# Schematic.net
KiCad netlist of a schematic drawn in EAGLE
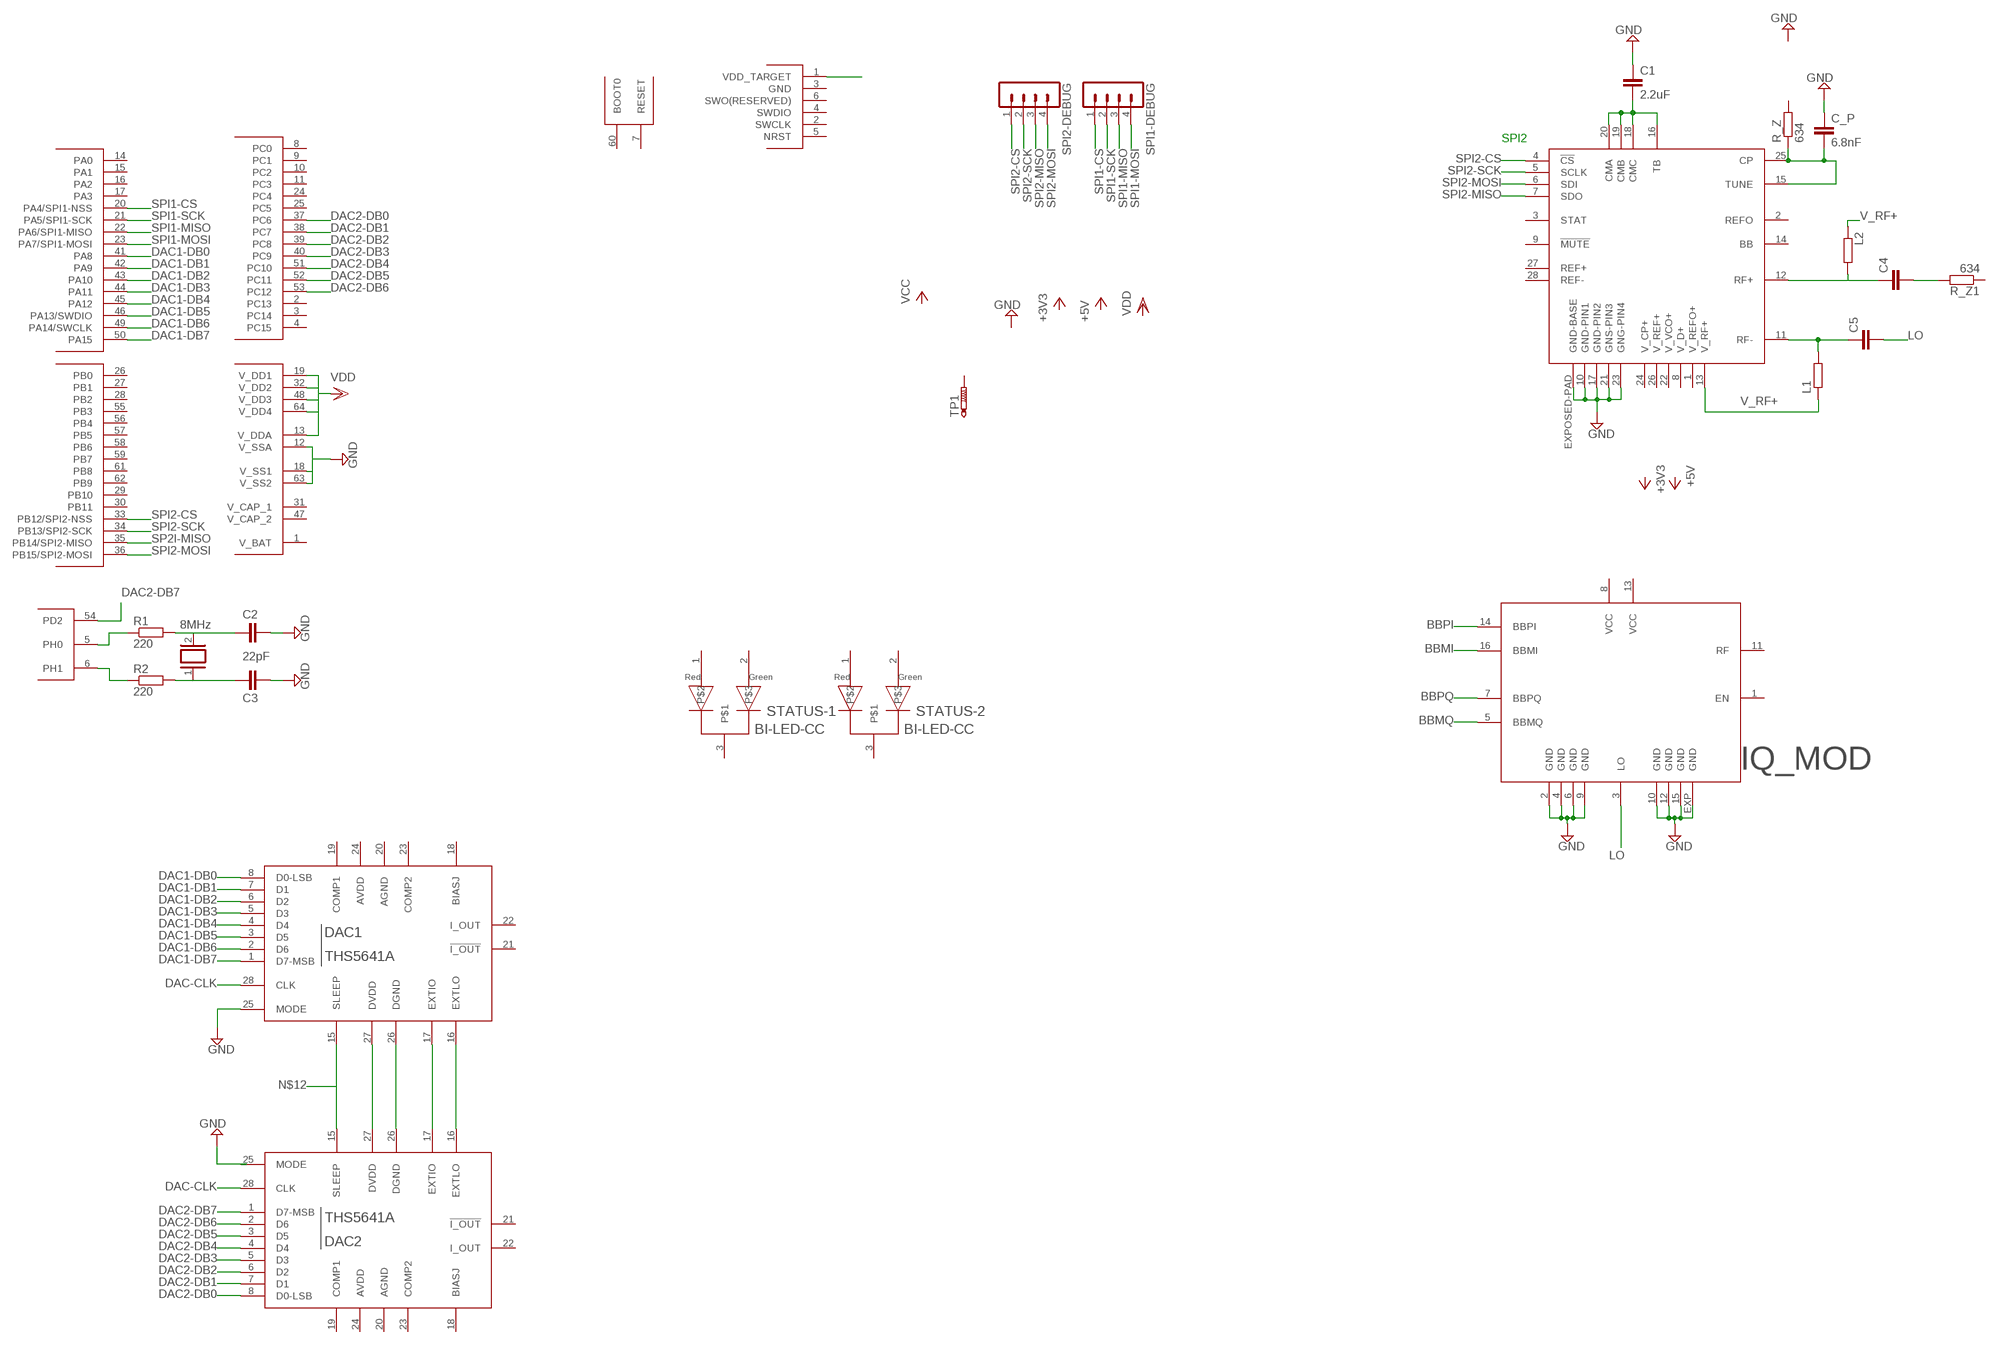
[diagram p0: schematic, sheet 1]

(export (version "E")
  (design (tool "Eeschema 10.0.6"))
  (components
    (comp (ref "C1")
      (value "2.2uF")
      (footprint "eagle-import:C0603")
      (libsource (lib "eagle-import") (part "C-EUC0603"))
    )
    (comp (ref "C2")
      (value "22pF")
      (footprint "eagle-import:C0603")
      (libsource (lib "eagle-import") (part "resistor_C-EUC0603"))
    )
    (comp (ref "C3")
      (value "22pF")
      (footprint "eagle-import:C0603")
      (libsource (lib "eagle-import") (part "resistor_C-EUC0603"))
    )
    (comp (ref "C4")
      (value "C-EUC1210")
      (footprint "eagle-import:C1210")
      (libsource (lib "eagle-import") (part "C-EUC1210"))
    )
    (comp (ref "C5")
      (value "C-EUC1210")
      (footprint "eagle-import:C1210")
      (libsource (lib "eagle-import") (part "C-EUC1210"))
    )
    (comp (ref "C_P")
      (value "6.8nF")
      (footprint "eagle-import:C0805")
      (libsource (lib "eagle-import") (part "resistor_C-EUC0805"))
    )
    (comp (ref "DAC1")
      (value "THS5641A")
      (footprint "eagle-import:SO28")
      (libsource (lib "eagle-import") (part "THS5641A"))
    )
    (comp (ref "DAC2")
      (value "THS5641A")
      (footprint "eagle-import:SO28")
      (libsource (lib "eagle-import") (part "THS5641A"))
    )
    (comp (ref "IQ_MOD")
      (value "LT5568")
      (footprint "eagle-import:QFN-16")
      (libsource (lib "eagle-import") (part "LT5568"))
    )
    (comp (ref "L1")
      (value "R-EU_R0402")
      (footprint "eagle-import:R0402")
      (libsource (lib "eagle-import") (part "R-EU_R0402"))
    )
    (comp (ref "L2")
      (value "R-EU_R0402")
      (footprint "eagle-import:R0402")
      (libsource (lib "eagle-import") (part "R-EU_R0402"))
    )
    (comp (ref "Q1")
      (value "8MHz")
      (footprint "eagle-import:QS")
      (libsource (lib "eagle-import") (part "XTAL/S"))
    )
    (comp (ref "R1")
      (value "220")
      (footprint "eagle-import:R0603")
      (libsource (lib "eagle-import") (part "resistor_R-EU_R0603"))
    )
    (comp (ref "R2")
      (value "220")
      (footprint "eagle-import:R0603")
      (libsource (lib "eagle-import") (part "resistor_R-EU_R0603"))
    )
    (comp (ref "R_Z")
      (value "634")
      (footprint "eagle-import:R0805")
      (libsource (lib "eagle-import") (part "R-EU_R0805"))
    )
    (comp (ref "R_Z1")
      (value "634")
      (footprint "eagle-import:R0805")
      (libsource (lib "eagle-import") (part "R-EU_R0805"))
    )
    (comp (ref "SPI1-DEBUG")
      (value "MA04-1")
      (footprint "eagle-import:MA04-1")
      (libsource (lib "eagle-import") (part "MA04-1"))
    )
    (comp (ref "SPI2-DEBUG")
      (value "MA04-1")
      (footprint "eagle-import:MA04-1")
      (libsource (lib "eagle-import") (part "MA04-1"))
    )
    (comp (ref "STATUS-1")
      (value "BI-LED-CC")
      (footprint "eagle-import:SOT-23")
      (libsource (lib "eagle-import") (part "BI-LED-CC"))
    )
    (comp (ref "STATUS-2")
      (value "BI-LED-CC")
      (footprint "eagle-import:SOT-23")
      (libsource (lib "eagle-import") (part "BI-LED-CC"))
    )
    (comp (ref "TP1")
      (value "PTR1PAD1-20Y")
      (footprint "eagle-import:P1-20Y")
      (libsource (lib "eagle-import") (part "PTR1PAD1-20Y"))
    )
    (comp (ref "U$1")
      (value "STM32F415RGT6")
      (footprint "eagle-import:LQFP-64")
      (libsource (lib "eagle-import") (part "STM32F415RGT6"))
    )
    (comp (ref "U$2")
      (value "SWD-HEADER")
      (footprint "eagle-import:6PIN-HEADER")
      (libsource (lib "eagle-import") (part "SWD-HEADER"))
    )
    (comp (ref "U$3")
      (value "LTC6946")
      (footprint "eagle-import:QFN-28")
      (libsource (lib "eagle-import") (part "LTC6946"))
    )
  )
  (nets
    (net (code "3") (name "/BBMI") (class "Default")
      (node (ref "IQ_MOD") (pin "16") (pinfunction "BBMI_16") (pintype "bidirectional"))
    )
    (net (code "4") (name "/BBMQ") (class "Default")
      (node (ref "IQ_MOD") (pin "5") (pinfunction "BBMQ_5") (pintype "bidirectional"))
    )
    (net (code "5") (name "/BBPI") (class "Default")
      (node (ref "IQ_MOD") (pin "14") (pinfunction "BBPI_14") (pintype "bidirectional"))
    )
    (net (code "6") (name "/BBPQ") (class "Default")
      (node (ref "IQ_MOD") (pin "7") (pinfunction "BBPQ_7") (pintype "bidirectional"))
    )
    (net (code "7") (name "/DAC-CLK") (class "Default")
      (node (ref "DAC1") (pin "28") (pinfunction "CLK_28") (pintype "bidirectional"))
      (node (ref "DAC2") (pin "28") (pinfunction "CLK_28") (pintype "bidirectional"))
    )
    (net (code "8") (name "/DAC1-DB0") (class "Default")
      (node (ref "DAC1") (pin "8") (pinfunction "D0-LSB_8") (pintype "bidirectional"))
      (node (ref "U$1") (pin "41") (pinfunction "PA8_41") (pintype "bidirectional"))
    )
    (net (code "9") (name "/DAC1-DB1") (class "Default")
      (node (ref "DAC1") (pin "7") (pinfunction "D1_7") (pintype "bidirectional"))
      (node (ref "U$1") (pin "42") (pinfunction "PA9_42") (pintype "bidirectional"))
    )
    (net (code "10") (name "/DAC1-DB2") (class "Default")
      (node (ref "DAC1") (pin "6") (pinfunction "D2_6") (pintype "bidirectional"))
      (node (ref "U$1") (pin "43") (pinfunction "PA10_43") (pintype "bidirectional"))
    )
    (net (code "11") (name "/DAC1-DB3") (class "Default")
      (node (ref "DAC1") (pin "5") (pinfunction "D3_5") (pintype "bidirectional"))
      (node (ref "U$1") (pin "44") (pinfunction "PA11_44") (pintype "bidirectional"))
    )
    (net (code "12") (name "/DAC1-DB4") (class "Default")
      (node (ref "DAC1") (pin "4") (pinfunction "D4_4") (pintype "bidirectional"))
      (node (ref "U$1") (pin "45") (pinfunction "PA12_45") (pintype "bidirectional"))
    )
    (net (code "13") (name "/DAC1-DB5") (class "Default")
      (node (ref "DAC1") (pin "3") (pinfunction "D5_3") (pintype "bidirectional"))
      (node (ref "U$1") (pin "46") (pinfunction "PA13/SWDIO_46") (pintype "bidirectional"))
    )
    (net (code "14") (name "/DAC1-DB6") (class "Default")
      (node (ref "DAC1") (pin "2") (pinfunction "D6_2") (pintype "bidirectional"))
      (node (ref "U$1") (pin "49") (pinfunction "PA14/SWCLK_49") (pintype "bidirectional"))
    )
    (net (code "15") (name "/DAC1-DB7") (class "Default")
      (node (ref "DAC1") (pin "1") (pinfunction "D7-MSB_1") (pintype "bidirectional"))
      (node (ref "U$1") (pin "50") (pinfunction "PA15_50") (pintype "bidirectional"))
    )
    (net (code "16") (name "/DAC2-DB0") (class "Default")
      (node (ref "DAC2") (pin "8") (pinfunction "D0-LSB_8") (pintype "bidirectional"))
      (node (ref "U$1") (pin "37") (pinfunction "PC6_37") (pintype "bidirectional"))
    )
    (net (code "17") (name "/DAC2-DB1") (class "Default")
      (node (ref "DAC2") (pin "7") (pinfunction "D1_7") (pintype "bidirectional"))
      (node (ref "U$1") (pin "38") (pinfunction "PC7_38") (pintype "bidirectional"))
    )
    (net (code "18") (name "/DAC2-DB2") (class "Default")
      (node (ref "DAC2") (pin "6") (pinfunction "D2_6") (pintype "bidirectional"))
      (node (ref "U$1") (pin "39") (pinfunction "PC8_39") (pintype "bidirectional"))
    )
    (net (code "19") (name "/DAC2-DB3") (class "Default")
      (node (ref "DAC2") (pin "5") (pinfunction "D3_5") (pintype "bidirectional"))
      (node (ref "U$1") (pin "40") (pinfunction "PC9_40") (pintype "bidirectional"))
    )
    (net (code "20") (name "/DAC2-DB4") (class "Default")
      (node (ref "DAC2") (pin "4") (pinfunction "D4_4") (pintype "bidirectional"))
      (node (ref "U$1") (pin "51") (pinfunction "PC10_51") (pintype "bidirectional"))
    )
    (net (code "21") (name "/DAC2-DB5") (class "Default")
      (node (ref "DAC2") (pin "3") (pinfunction "D5_3") (pintype "bidirectional"))
      (node (ref "U$1") (pin "52") (pinfunction "PC11_52") (pintype "bidirectional"))
    )
    (net (code "22") (name "/DAC2-DB6") (class "Default")
      (node (ref "DAC2") (pin "2") (pinfunction "D6_2") (pintype "bidirectional"))
      (node (ref "U$1") (pin "53") (pinfunction "PC12_53") (pintype "bidirectional"))
    )
    (net (code "23") (name "/DAC2-DB7") (class "Default")
      (node (ref "DAC2") (pin "1") (pinfunction "D7-MSB_1") (pintype "bidirectional"))
      (node (ref "U$1") (pin "54") (pinfunction "PD2_54") (pintype "bidirectional"))
    )
    (net (code "24") (name "/LO") (class "Default")
      (node (ref "C5") (pin "2") (pinfunction "2_2") (pintype "passive"))
      (node (ref "IQ_MOD") (pin "3") (pinfunction "LO_3") (pintype "bidirectional"))
    )
    (net (code "25") (name "/N$12") (class "Default")
      (node (ref "DAC1") (pin "15") (pinfunction "SLEEP_15") (pintype "bidirectional"))
      (node (ref "DAC2") (pin "15") (pinfunction "SLEEP_15") (pintype "bidirectional"))
    )
    (net (code "26") (name "/SP2I-MISO") (class "Default")
      (node (ref "U$1") (pin "35") (pinfunction "PB14/SPI2-MISO_35") (pintype "bidirectional"))
    )
    (net (code "27") (name "/SPI1-CS") (class "Default")
      (node (ref "SPI1-DEBUG") (pin "1") (pinfunction "1_1") (pintype "passive"))
      (node (ref "U$1") (pin "20") (pinfunction "PA4/SPI1-NSS_20") (pintype "bidirectional"))
    )
    (net (code "28") (name "/SPI1-MISO") (class "Default")
      (node (ref "SPI1-DEBUG") (pin "3") (pinfunction "3_3") (pintype "passive"))
      (node (ref "U$1") (pin "22") (pinfunction "PA6/SPI1-MISO_22") (pintype "bidirectional"))
    )
    (net (code "29") (name "/SPI1-MOSI") (class "Default")
      (node (ref "SPI1-DEBUG") (pin "4") (pinfunction "4_4") (pintype "passive"))
      (node (ref "U$1") (pin "23") (pinfunction "PA7/SPI1-MOSI_23") (pintype "bidirectional"))
    )
    (net (code "30") (name "/SPI1-SCK") (class "Default")
      (node (ref "SPI1-DEBUG") (pin "2") (pinfunction "2_2") (pintype "passive"))
      (node (ref "U$1") (pin "21") (pinfunction "PA5/SPI1-SCK_21") (pintype "bidirectional"))
    )
    (net (code "31") (name "/SPI2-CS") (class "Default")
      (node (ref "SPI2-DEBUG") (pin "1") (pinfunction "1_1") (pintype "passive"))
      (node (ref "U$1") (pin "33") (pinfunction "PB12/SPI2-NSS_33") (pintype "bidirectional"))
      (node (ref "U$3") (pin "4") (pinfunction "~{CS}_4") (pintype "bidirectional"))
    )
    (net (code "32") (name "/SPI2-MISO") (class "Default")
      (node (ref "SPI2-DEBUG") (pin "3") (pinfunction "3_3") (pintype "passive"))
      (node (ref "U$3") (pin "7") (pinfunction "SDO_7") (pintype "bidirectional"))
    )
    (net (code "33") (name "/SPI2-MOSI") (class "Default")
      (node (ref "SPI2-DEBUG") (pin "4") (pinfunction "4_4") (pintype "passive"))
      (node (ref "U$1") (pin "36") (pinfunction "PB15/SPI2-MOSI_36") (pintype "bidirectional"))
      (node (ref "U$3") (pin "6") (pinfunction "SDI_6") (pintype "bidirectional"))
    )
    (net (code "34") (name "/SPI2-SCK") (class "Default")
      (node (ref "SPI2-DEBUG") (pin "2") (pinfunction "2_2") (pintype "passive"))
      (node (ref "U$1") (pin "34") (pinfunction "PB13/SPI2-SCK_34") (pintype "bidirectional"))
      (node (ref "U$3") (pin "5") (pinfunction "SCLK_5") (pintype "bidirectional"))
    )
    (net (code "35") (name "/V_RF+") (class "Default")
      (node (ref "L1") (pin "1") (pinfunction "1_1") (pintype "passive"))
      (node (ref "L2") (pin "1") (pinfunction "1_1") (pintype "passive"))
      (node (ref "U$3") (pin "13") (pinfunction "V_RF+_13") (pintype "bidirectional"))
    )
    (net (code "36") (name "GND") (class "Default")
      (node (ref "C1") (pin "1") (pinfunction "1_1") (pintype "passive"))
      (node (ref "C2") (pin "2") (pinfunction "2_2") (pintype "passive"))
      (node (ref "C3") (pin "2") (pinfunction "2_2") (pintype "passive"))
      (node (ref "C_P") (pin "1") (pinfunction "1_1") (pintype "passive"))
      (node (ref "DAC1") (pin "25") (pinfunction "MODE_25") (pintype "bidirectional"))
      (node (ref "IQ_MOD") (pin "10") (pinfunction "GND_10") (pintype "bidirectional"))
      (node (ref "IQ_MOD") (pin "12") (pinfunction "GND_12") (pintype "bidirectional"))
      (node (ref "IQ_MOD") (pin "15") (pinfunction "GND_15") (pintype "bidirectional"))
      (node (ref "IQ_MOD") (pin "2") (pinfunction "GND_2") (pintype "bidirectional"))
      (node (ref "IQ_MOD") (pin "4") (pinfunction "GND_4") (pintype "bidirectional"))
      (node (ref "IQ_MOD") (pin "6") (pinfunction "GND_6") (pintype "bidirectional"))
      (node (ref "IQ_MOD") (pin "9") (pinfunction "GND_9") (pintype "bidirectional"))
      (node (ref "IQ_MOD") (pin "EXP") (pinfunction "GND_EXP") (pintype "bidirectional"))
      (node (ref "U$1") (pin "12") (pinfunction "V_SSA_12") (pintype "bidirectional"))
      (node (ref "U$1") (pin "18") (pinfunction "V_SS1_18") (pintype "bidirectional"))
      (node (ref "U$1") (pin "63") (pinfunction "V_SS2_63") (pintype "bidirectional"))
      (node (ref "U$3") (pin "10") (pinfunction "GND-PIN1_10") (pintype "bidirectional"))
      (node (ref "U$3") (pin "17") (pinfunction "GND-PIN2_17") (pintype "bidirectional"))
      (node (ref "U$3") (pin "21") (pinfunction "GNS-PIN3_21") (pintype "bidirectional"))
      (node (ref "U$3") (pin "23") (pinfunction "GNG-PIN4_23") (pintype "bidirectional"))
      (node (ref "U$3") (pin "EXPOSED-PAD") (pinfunction "GND-BASE_EXPOSED-PAD") (pintype "bidirectional"))
    )
    (net (code "37") (name "Net-(C2-Pad1)") (class "Default")
      (node (ref "C2") (pin "1") (pinfunction "1_1") (pintype "passive"))
      (node (ref "Q1") (pin "2") (pinfunction "2_2") (pintype "passive"))
      (node (ref "R1") (pin "2") (pinfunction "2_2") (pintype "passive"))
    )
    (net (code "38") (name "Net-(C3-Pad1)") (class "Default")
      (node (ref "C3") (pin "1") (pinfunction "1_1") (pintype "passive"))
      (node (ref "Q1") (pin "1") (pinfunction "1_1") (pintype "passive"))
      (node (ref "R2") (pin "2") (pinfunction "2_2") (pintype "passive"))
    )
    (net (code "39") (name "Net-(C4-Pad2)") (class "Default")
      (node (ref "C4") (pin "2") (pinfunction "2_2") (pintype "passive"))
      (node (ref "R_Z1") (pin "2") (pinfunction "2_2") (pintype "passive"))
    )
    (net (code "40") (name "Net-(DAC1-DGND)") (class "Default")
      (node (ref "DAC1") (pin "26") (pinfunction "DGND_26") (pintype "bidirectional"))
      (node (ref "DAC2") (pin "26") (pinfunction "DGND_26") (pintype "bidirectional"))
    )
    (net (code "41") (name "Net-(DAC1-DVDD)") (class "Default")
      (node (ref "DAC1") (pin "27") (pinfunction "DVDD_27") (pintype "bidirectional"))
      (node (ref "DAC2") (pin "27") (pinfunction "DVDD_27") (pintype "bidirectional"))
    )
    (net (code "42") (name "Net-(DAC1-EXTIO)") (class "Default")
      (node (ref "DAC1") (pin "17") (pinfunction "EXTIO_17") (pintype "bidirectional"))
      (node (ref "DAC2") (pin "17") (pinfunction "EXTIO_17") (pintype "bidirectional"))
    )
    (net (code "43") (name "Net-(DAC1-EXTLO)") (class "Default")
      (node (ref "DAC1") (pin "16") (pinfunction "EXTLO_16") (pintype "bidirectional"))
      (node (ref "DAC2") (pin "16") (pinfunction "EXTLO_16") (pintype "bidirectional"))
    )
    (net (code "44") (name "Net-(U$1B-PH0)") (class "Default")
      (node (ref "R1") (pin "1") (pinfunction "1_1") (pintype "passive"))
      (node (ref "U$1") (pin "5") (pinfunction "PH0_5") (pintype "bidirectional"))
    )
    (net (code "45") (name "Net-(U$1B-PH1)") (class "Default")
      (node (ref "R2") (pin "1") (pinfunction "1_1") (pintype "passive"))
      (node (ref "U$1") (pin "6") (pinfunction "PH1_6") (pintype "bidirectional"))
    )
    (net (code "46") (name "Net-(U$3-CMA)") (class "Default")
      (node (ref "C1") (pin "2") (pinfunction "2_2") (pintype "passive"))
      (node (ref "U$3") (pin "16") (pinfunction "TB_16") (pintype "bidirectional"))
      (node (ref "U$3") (pin "18") (pinfunction "CMC_18") (pintype "bidirectional"))
      (node (ref "U$3") (pin "19") (pinfunction "CMB_19") (pintype "bidirectional"))
      (node (ref "U$3") (pin "20") (pinfunction "CMA_20") (pintype "bidirectional"))
    )
    (net (code "47") (name "Net-(U$3-CP)") (class "Default")
      (node (ref "C_P") (pin "2") (pinfunction "2_2") (pintype "passive"))
      (node (ref "R_Z") (pin "1") (pinfunction "1_1") (pintype "passive"))
      (node (ref "U$3") (pin "15") (pinfunction "TUNE_15") (pintype "bidirectional"))
      (node (ref "U$3") (pin "25") (pinfunction "CP_25") (pintype "bidirectional"))
    )
    (net (code "48") (name "Net-(U$3-RF+)") (class "Default")
      (node (ref "C4") (pin "1") (pinfunction "1_1") (pintype "passive"))
      (node (ref "L2") (pin "2") (pinfunction "2_2") (pintype "passive"))
      (node (ref "U$3") (pin "12") (pinfunction "RF+_12") (pintype "bidirectional"))
    )
    (net (code "49") (name "Net-(U$3-RF-)") (class "Default")
      (node (ref "C5") (pin "1") (pinfunction "1_1") (pintype "passive"))
      (node (ref "L1") (pin "2") (pinfunction "2_2") (pintype "passive"))
      (node (ref "U$3") (pin "11") (pinfunction "RF-_11") (pintype "bidirectional"))
    )
    (net (code "51") (name "VDD") (class "Default")
      (node (ref "U$1") (pin "13") (pinfunction "V_DDA_13") (pintype "bidirectional"))
      (node (ref "U$1") (pin "19") (pinfunction "V_DD1_19") (pintype "bidirectional"))
      (node (ref "U$1") (pin "32") (pinfunction "V_DD2_32") (pintype "bidirectional"))
      (node (ref "U$1") (pin "48") (pinfunction "V_DD3_48") (pintype "bidirectional"))
      (node (ref "U$1") (pin "64") (pinfunction "V_DD4_64") (pintype "bidirectional"))
    )
    (net (code "52") (name "unconnected-(DAC1-AGND-Pad20)") (class "Default")
      (node (ref "DAC1") (pin "20") (pinfunction "AGND_20") (pintype "bidirectional"))
    )
    (net (code "53") (name "unconnected-(DAC1-AVDD-Pad24)") (class "Default")
      (node (ref "DAC1") (pin "24") (pinfunction "AVDD_24") (pintype "bidirectional"))
    )
    (net (code "54") (name "unconnected-(DAC1-BIASJ-Pad18)") (class "Default")
      (node (ref "DAC1") (pin "18") (pinfunction "BIASJ_18") (pintype "bidirectional"))
    )
    (net (code "55") (name "unconnected-(DAC1-COMP1-Pad19)") (class "Default")
      (node (ref "DAC1") (pin "19") (pinfunction "COMP1_19") (pintype "bidirectional"))
    )
    (net (code "56") (name "unconnected-(DAC1-COMP2-Pad23)") (class "Default")
      (node (ref "DAC1") (pin "23") (pinfunction "COMP2_23") (pintype "bidirectional"))
    )
    (net (code "57") (name "unconnected-(DAC1-I_OUT-Pad22)") (class "Default")
      (node (ref "DAC1") (pin "22") (pinfunction "I_OUT_22") (pintype "bidirectional"))
    )
    (net (code "58") (name "unconnected-(DAC1-~{I_OUT}-Pad21)") (class "Default")
      (node (ref "DAC1") (pin "21") (pinfunction "~{I_OUT}_21") (pintype "bidirectional"))
    )
    (net (code "59") (name "unconnected-(DAC2-AGND-Pad20)") (class "Default")
      (node (ref "DAC2") (pin "20") (pinfunction "AGND_20") (pintype "bidirectional"))
    )
    (net (code "60") (name "unconnected-(DAC2-AVDD-Pad24)") (class "Default")
      (node (ref "DAC2") (pin "24") (pinfunction "AVDD_24") (pintype "bidirectional"))
    )
    (net (code "61") (name "unconnected-(DAC2-BIASJ-Pad18)") (class "Default")
      (node (ref "DAC2") (pin "18") (pinfunction "BIASJ_18") (pintype "bidirectional"))
    )
    (net (code "62") (name "unconnected-(DAC2-COMP1-Pad19)") (class "Default")
      (node (ref "DAC2") (pin "19") (pinfunction "COMP1_19") (pintype "bidirectional"))
    )
    (net (code "63") (name "unconnected-(DAC2-COMP2-Pad23)") (class "Default")
      (node (ref "DAC2") (pin "23") (pinfunction "COMP2_23") (pintype "bidirectional"))
    )
    (net (code "64") (name "unconnected-(DAC2-I_OUT-Pad22)") (class "Default")
      (node (ref "DAC2") (pin "22") (pinfunction "I_OUT_22") (pintype "bidirectional"))
    )
    (net (code "65") (name "unconnected-(DAC2-MODE-Pad25)") (class "Default")
      (node (ref "DAC2") (pin "25") (pinfunction "MODE_25") (pintype "bidirectional"))
    )
    (net (code "66") (name "unconnected-(DAC2-~{I_OUT}-Pad21)") (class "Default")
      (node (ref "DAC2") (pin "21") (pinfunction "~{I_OUT}_21") (pintype "bidirectional"))
    )
    (net (code "67") (name "unconnected-(IQ_MOD-EN-Pad1)") (class "Default")
      (node (ref "IQ_MOD") (pin "1") (pinfunction "EN_1") (pintype "bidirectional"))
    )
    (net (code "68") (name "unconnected-(IQ_MOD-RF-Pad11)") (class "Default")
      (node (ref "IQ_MOD") (pin "11") (pinfunction "RF_11") (pintype "bidirectional"))
    )
    (net (code "69") (name "unconnected-(IQ_MOD-VCC-Pad8)") (class "Default")
      (node (ref "IQ_MOD") (pin "8") (pinfunction "VCC_8") (pintype "bidirectional"))
    )
    (net (code "70") (name "unconnected-(IQ_MOD-VCC-Pad13)") (class "Default")
      (node (ref "IQ_MOD") (pin "13") (pinfunction "VCC_13") (pintype "bidirectional"))
    )
    (net (code "71") (name "unconnected-(R_Z-Pad2)") (class "Default")
      (node (ref "R_Z") (pin "2") (pinfunction "2_2") (pintype "passive"))
    )
    (net (code "72") (name "unconnected-(R_Z1-Pad1)") (class "Default")
      (node (ref "R_Z1") (pin "1") (pinfunction "1_1") (pintype "passive"))
    )
    (net (code "73") (name "unconnected-(STATUS-1-P$1-Pad3)") (class "Default")
      (node (ref "STATUS-1") (pin "3") (pinfunction "P$1_3") (pintype "bidirectional"))
    )
    (net (code "74") (name "unconnected-(STATUS-1-P$2-Pad1)") (class "Default")
      (node (ref "STATUS-1") (pin "1") (pinfunction "P$2_1") (pintype "bidirectional"))
    )
    (net (code "75") (name "unconnected-(STATUS-1-P$3-Pad2)") (class "Default")
      (node (ref "STATUS-1") (pin "2") (pinfunction "P$3_2") (pintype "bidirectional"))
    )
    (net (code "76") (name "unconnected-(STATUS-2-P$1-Pad3)") (class "Default")
      (node (ref "STATUS-2") (pin "3") (pinfunction "P$1_3") (pintype "bidirectional"))
    )
    (net (code "77") (name "unconnected-(STATUS-2-P$2-Pad1)") (class "Default")
      (node (ref "STATUS-2") (pin "1") (pinfunction "P$2_1") (pintype "bidirectional"))
    )
    (net (code "78") (name "unconnected-(STATUS-2-P$3-Pad2)") (class "Default")
      (node (ref "STATUS-2") (pin "2") (pinfunction "P$3_2") (pintype "bidirectional"))
    )
    (net (code "79") (name "unconnected-(TP1-PadTP)") (class "Default")
      (node (ref "TP1") (pin "TP") (pinfunction "TP_TP") (pintype "input"))
    )
    (net (code "80") (name "unconnected-(U$1A-BOOT0-Pad60)") (class "Default")
      (node (ref "U$1") (pin "60") (pinfunction "BOOT0_60") (pintype "bidirectional"))
    )
    (net (code "81") (name "unconnected-(U$1A-RESET-Pad7)") (class "Default")
      (node (ref "U$1") (pin "7") (pinfunction "RESET_7") (pintype "bidirectional"))
    )
    (net (code "82") (name "unconnected-(U$1C-PA0-Pad14)") (class "Default")
      (node (ref "U$1") (pin "14") (pinfunction "PA0_14") (pintype "bidirectional"))
    )
    (net (code "83") (name "unconnected-(U$1C-PA1-Pad15)") (class "Default")
      (node (ref "U$1") (pin "15") (pinfunction "PA1_15") (pintype "bidirectional"))
    )
    (net (code "84") (name "unconnected-(U$1C-PA2-Pad16)") (class "Default")
      (node (ref "U$1") (pin "16") (pinfunction "PA2_16") (pintype "bidirectional"))
    )
    (net (code "85") (name "unconnected-(U$1C-PA3-Pad17)") (class "Default")
      (node (ref "U$1") (pin "17") (pinfunction "PA3_17") (pintype "bidirectional"))
    )
    (net (code "86") (name "unconnected-(U$1D-PB0-Pad26)") (class "Default")
      (node (ref "U$1") (pin "26") (pinfunction "PB0_26") (pintype "bidirectional"))
    )
    (net (code "87") (name "unconnected-(U$1D-PB1-Pad27)") (class "Default")
      (node (ref "U$1") (pin "27") (pinfunction "PB1_27") (pintype "bidirectional"))
    )
    (net (code "88") (name "unconnected-(U$1D-PB2-Pad28)") (class "Default")
      (node (ref "U$1") (pin "28") (pinfunction "PB2_28") (pintype "bidirectional"))
    )
    (net (code "89") (name "unconnected-(U$1D-PB3-Pad55)") (class "Default")
      (node (ref "U$1") (pin "55") (pinfunction "PB3_55") (pintype "bidirectional"))
    )
    (net (code "90") (name "unconnected-(U$1D-PB4-Pad56)") (class "Default")
      (node (ref "U$1") (pin "56") (pinfunction "PB4_56") (pintype "bidirectional"))
    )
    (net (code "91") (name "unconnected-(U$1D-PB5-Pad57)") (class "Default")
      (node (ref "U$1") (pin "57") (pinfunction "PB5_57") (pintype "bidirectional"))
    )
    (net (code "92") (name "unconnected-(U$1D-PB6-Pad58)") (class "Default")
      (node (ref "U$1") (pin "58") (pinfunction "PB6_58") (pintype "bidirectional"))
    )
    (net (code "93") (name "unconnected-(U$1D-PB7-Pad59)") (class "Default")
      (node (ref "U$1") (pin "59") (pinfunction "PB7_59") (pintype "bidirectional"))
    )
    (net (code "94") (name "unconnected-(U$1D-PB8-Pad61)") (class "Default")
      (node (ref "U$1") (pin "61") (pinfunction "PB8_61") (pintype "bidirectional"))
    )
    (net (code "95") (name "unconnected-(U$1D-PB9-Pad62)") (class "Default")
      (node (ref "U$1") (pin "62") (pinfunction "PB9_62") (pintype "bidirectional"))
    )
    (net (code "96") (name "unconnected-(U$1D-PB10-Pad29)") (class "Default")
      (node (ref "U$1") (pin "29") (pinfunction "PB10_29") (pintype "bidirectional"))
    )
    (net (code "97") (name "unconnected-(U$1D-PB11-Pad30)") (class "Default")
      (node (ref "U$1") (pin "30") (pinfunction "PB11_30") (pintype "bidirectional"))
    )
    (net (code "98") (name "unconnected-(U$1E-PC0-Pad8)") (class "Default")
      (node (ref "U$1") (pin "8") (pinfunction "PC0_8") (pintype "bidirectional"))
    )
    (net (code "99") (name "unconnected-(U$1E-PC1-Pad9)") (class "Default")
      (node (ref "U$1") (pin "9") (pinfunction "PC1_9") (pintype "bidirectional"))
    )
    (net (code "100") (name "unconnected-(U$1E-PC2-Pad10)") (class "Default")
      (node (ref "U$1") (pin "10") (pinfunction "PC2_10") (pintype "bidirectional"))
    )
    (net (code "101") (name "unconnected-(U$1E-PC3-Pad11)") (class "Default")
      (node (ref "U$1") (pin "11") (pinfunction "PC3_11") (pintype "bidirectional"))
    )
    (net (code "102") (name "unconnected-(U$1E-PC4-Pad24)") (class "Default")
      (node (ref "U$1") (pin "24") (pinfunction "PC4_24") (pintype "bidirectional"))
    )
    (net (code "103") (name "unconnected-(U$1E-PC5-Pad25)") (class "Default")
      (node (ref "U$1") (pin "25") (pinfunction "PC5_25") (pintype "bidirectional"))
    )
    (net (code "104") (name "unconnected-(U$1E-PC13-Pad2)") (class "Default")
      (node (ref "U$1") (pin "2") (pinfunction "PC13_2") (pintype "bidirectional"))
    )
    (net (code "105") (name "unconnected-(U$1E-PC14-Pad3)") (class "Default")
      (node (ref "U$1") (pin "3") (pinfunction "PC14_3") (pintype "bidirectional"))
    )
    (net (code "106") (name "unconnected-(U$1E-PC15-Pad4)") (class "Default")
      (node (ref "U$1") (pin "4") (pinfunction "PC15_4") (pintype "bidirectional"))
    )
    (net (code "107") (name "unconnected-(U$1F-V_BAT-Pad1)") (class "Default")
      (node (ref "U$1") (pin "1") (pinfunction "V_BAT_1") (pintype "bidirectional"))
    )
    (net (code "108") (name "unconnected-(U$1F-V_CAP_1-Pad31)") (class "Default")
      (node (ref "U$1") (pin "31") (pinfunction "V_CAP_1_31") (pintype "bidirectional"))
    )
    (net (code "109") (name "unconnected-(U$1F-V_CAP_2-Pad47)") (class "Default")
      (node (ref "U$1") (pin "47") (pinfunction "V_CAP_2_47") (pintype "bidirectional"))
    )
    (net (code "110") (name "unconnected-(U$2-GND-Pad3)") (class "Default")
      (node (ref "U$2") (pin "3") (pinfunction "GND_3") (pintype "bidirectional"))
    )
    (net (code "111") (name "unconnected-(U$2-NRST-Pad5)") (class "Default")
      (node (ref "U$2") (pin "5") (pinfunction "NRST_5") (pintype "bidirectional"))
    )
    (net (code "112") (name "unconnected-(U$2-SWCLK-Pad2)") (class "Default")
      (node (ref "U$2") (pin "2") (pinfunction "SWCLK_2") (pintype "bidirectional"))
    )
    (net (code "113") (name "unconnected-(U$2-SWDIO-Pad4)") (class "Default")
      (node (ref "U$2") (pin "4") (pinfunction "SWDIO_4") (pintype "bidirectional"))
    )
    (net (code "114") (name "unconnected-(U$2-SWO(RESERVED)-Pad6)") (class "Default")
      (node (ref "U$2") (pin "6") (pinfunction "SWO(RESERVED)_6") (pintype "bidirectional"))
    )
    (net (code "115") (name "unconnected-(U$2-VDD_TARGET-Pad1)") (class "Default")
      (node (ref "U$2") (pin "1") (pinfunction "VDD_TARGET_1") (pintype "bidirectional"))
    )
    (net (code "116") (name "unconnected-(U$3-BB-Pad14)") (class "Default")
      (node (ref "U$3") (pin "14") (pinfunction "BB_14") (pintype "bidirectional"))
    )
    (net (code "117") (name "unconnected-(U$3-REF+-Pad27)") (class "Default")
      (node (ref "U$3") (pin "27") (pinfunction "REF+_27") (pintype "bidirectional"))
    )
    (net (code "118") (name "unconnected-(U$3-REF--Pad28)") (class "Default")
      (node (ref "U$3") (pin "28") (pinfunction "REF-_28") (pintype "bidirectional"))
    )
    (net (code "119") (name "unconnected-(U$3-REFO-Pad2)") (class "Default")
      (node (ref "U$3") (pin "2") (pinfunction "REFO_2") (pintype "bidirectional"))
    )
    (net (code "120") (name "unconnected-(U$3-STAT-Pad3)") (class "Default")
      (node (ref "U$3") (pin "3") (pinfunction "STAT_3") (pintype "bidirectional"))
    )
    (net (code "121") (name "unconnected-(U$3-V_CP+-Pad24)") (class "Default")
      (node (ref "U$3") (pin "24") (pinfunction "V_CP+_24") (pintype "bidirectional"))
    )
    (net (code "122") (name "unconnected-(U$3-V_D+-Pad8)") (class "Default")
      (node (ref "U$3") (pin "8") (pinfunction "V_D+_8") (pintype "bidirectional"))
    )
    (net (code "123") (name "unconnected-(U$3-V_REF+-Pad26)") (class "Default")
      (node (ref "U$3") (pin "26") (pinfunction "V_REF+_26") (pintype "bidirectional"))
    )
    (net (code "124") (name "unconnected-(U$3-V_REFO+-Pad1)") (class "Default")
      (node (ref "U$3") (pin "1") (pinfunction "V_REFO+_1") (pintype "bidirectional"))
    )
    (net (code "125") (name "unconnected-(U$3-V_VCO+-Pad22)") (class "Default")
      (node (ref "U$3") (pin "22") (pinfunction "V_VCO+_22") (pintype "bidirectional"))
    )
    (net (code "126") (name "unconnected-(U$3-~{MUTE}-Pad9)") (class "Default")
      (node (ref "U$3") (pin "9") (pinfunction "~{MUTE}_9") (pintype "bidirectional"))
    )
  )
)
